# Controller_v_1.net
KiCad netlist of a schematic drawn in EAGLE
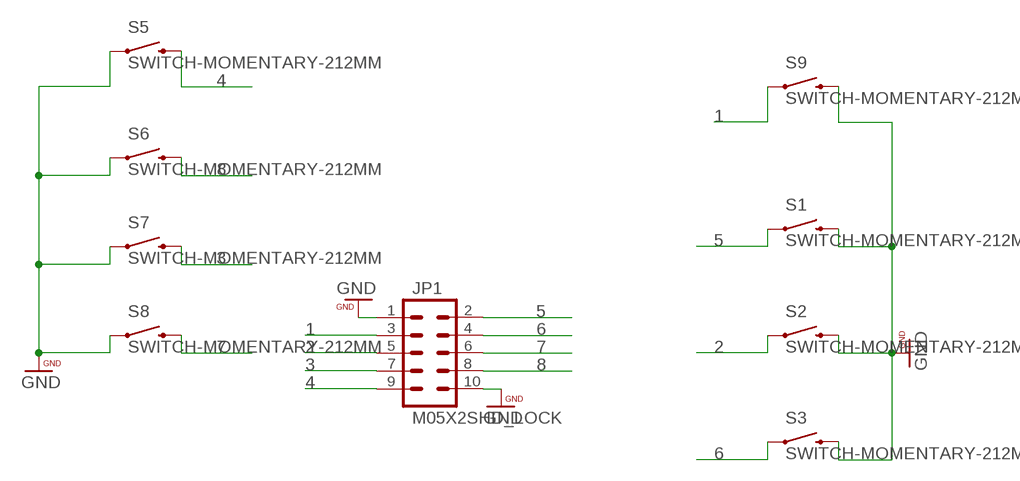
[diagram p0: schematic, sheet 1]

(export (version "E")
  (design (tool "Eeschema 10.0.6"))
  (components
    (comp (ref "JP1")
      (value "M05X2SHD_LOCK")
      (footprint "eagle-import:2X5-SHROUDED_LOCK")
      (libsource (lib "eagle-import") (part "M05X2SHD_LOCK"))
    )
    (comp (ref "S1")
      (value "SWITCH-MOMENTARY-212MM")
      (footprint "eagle-import:TACTILE-PTH-12MM")
      (libsource (lib "eagle-import") (part "SWITCH-MOMENTARY-212MM"))
    )
    (comp (ref "S2")
      (value "SWITCH-MOMENTARY-212MM")
      (footprint "eagle-import:TACTILE-PTH-12MM")
      (libsource (lib "eagle-import") (part "SWITCH-MOMENTARY-212MM"))
    )
    (comp (ref "S3")
      (value "SWITCH-MOMENTARY-212MM")
      (footprint "eagle-import:TACTILE-PTH-12MM")
      (libsource (lib "eagle-import") (part "SWITCH-MOMENTARY-212MM"))
    )
    (comp (ref "S5")
      (value "SWITCH-MOMENTARY-212MM")
      (footprint "eagle-import:TACTILE-PTH-12MM")
      (libsource (lib "eagle-import") (part "SWITCH-MOMENTARY-212MM"))
    )
    (comp (ref "S6")
      (value "SWITCH-MOMENTARY-212MM")
      (footprint "eagle-import:TACTILE-PTH-12MM")
      (libsource (lib "eagle-import") (part "SWITCH-MOMENTARY-212MM"))
    )
    (comp (ref "S7")
      (value "SWITCH-MOMENTARY-212MM")
      (footprint "eagle-import:TACTILE-PTH-12MM")
      (libsource (lib "eagle-import") (part "SWITCH-MOMENTARY-212MM"))
    )
    (comp (ref "S8")
      (value "SWITCH-MOMENTARY-212MM")
      (footprint "eagle-import:TACTILE-PTH-12MM")
      (libsource (lib "eagle-import") (part "SWITCH-MOMENTARY-212MM"))
    )
    (comp (ref "S9")
      (value "SWITCH-MOMENTARY-212MM")
      (footprint "eagle-import:TACTILE-PTH-12MM")
      (libsource (lib "eagle-import") (part "SWITCH-MOMENTARY-212MM"))
    )
  )
  (nets
    (net (code "1") (name "/1") (class "Default")
      (node (ref "JP1") (pin "3") (pinfunction "3_3") (pintype "passive"))
      (node (ref "S9") (pin "1") (pinfunction "1_1") (pintype "passive"))
    )
    (net (code "2") (name "/2") (class "Default")
      (node (ref "JP1") (pin "5") (pinfunction "5_5") (pintype "passive"))
      (node (ref "S2") (pin "1") (pinfunction "1_1") (pintype "passive"))
    )
    (net (code "3") (name "/3") (class "Default")
      (node (ref "JP1") (pin "7") (pinfunction "7_7") (pintype "passive"))
      (node (ref "S7") (pin "3") (pinfunction "2_3") (pintype "passive"))
    )
    (net (code "4") (name "/4") (class "Default")
      (node (ref "JP1") (pin "9") (pinfunction "9_9") (pintype "passive"))
      (node (ref "S5") (pin "3") (pinfunction "2_3") (pintype "passive"))
    )
    (net (code "5") (name "/5") (class "Default")
      (node (ref "JP1") (pin "2") (pinfunction "2_2") (pintype "passive"))
      (node (ref "S1") (pin "1") (pinfunction "1_1") (pintype "passive"))
    )
    (net (code "6") (name "/6") (class "Default")
      (node (ref "JP1") (pin "4") (pinfunction "4_4") (pintype "passive"))
      (node (ref "S3") (pin "1") (pinfunction "1_1") (pintype "passive"))
    )
    (net (code "7") (name "/7") (class "Default")
      (node (ref "JP1") (pin "6") (pinfunction "6_6") (pintype "passive"))
      (node (ref "S8") (pin "3") (pinfunction "2_3") (pintype "passive"))
    )
    (net (code "8") (name "/8") (class "Default")
      (node (ref "JP1") (pin "8") (pinfunction "8_8") (pintype "passive"))
      (node (ref "S6") (pin "3") (pinfunction "2_3") (pintype "passive"))
    )
    (net (code "9") (name "GND") (class "Default")
      (node (ref "JP1") (pin "1") (pinfunction "1_1") (pintype "passive"))
      (node (ref "JP1") (pin "10") (pinfunction "10_10") (pintype "passive"))
      (node (ref "S1") (pin "3") (pinfunction "2_3") (pintype "passive"))
      (node (ref "S2") (pin "3") (pinfunction "2_3") (pintype "passive"))
      (node (ref "S3") (pin "3") (pinfunction "2_3") (pintype "passive"))
      (node (ref "S5") (pin "1") (pinfunction "1_1") (pintype "passive"))
      (node (ref "S6") (pin "1") (pinfunction "1_1") (pintype "passive"))
      (node (ref "S7") (pin "1") (pinfunction "1_1") (pintype "passive"))
      (node (ref "S8") (pin "1") (pinfunction "1_1") (pintype "passive"))
      (node (ref "S9") (pin "3") (pinfunction "2_3") (pintype "passive"))
    )
  )
)
